# backplane.net
KiCad netlist of a schematic drawn in EAGLE
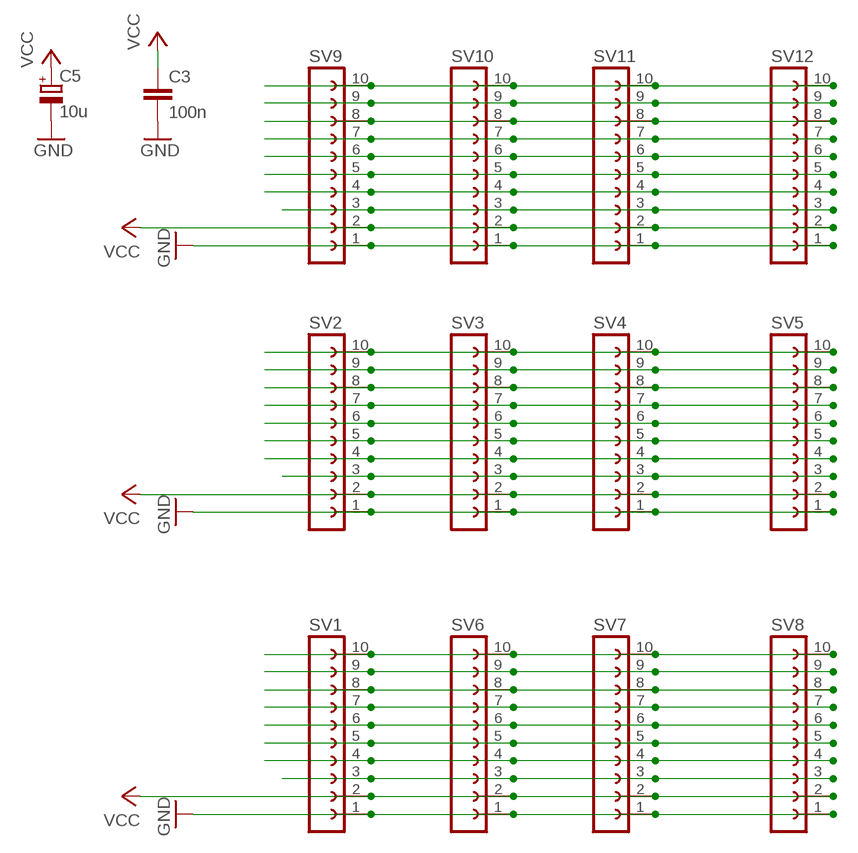
[diagram p0: schematic, sheet 1]

(export (version "E")
  (design (tool "Eeschema 10.0.6"))
  (components
    (comp (ref "C3")
      (value "100n")
      (footprint "eagle-import:C025-024X044")
      (libsource (lib "eagle-import") (part "C-EU025-024X044"))
    )
    (comp (ref "C5")
      (value "10u")
      (footprint "eagle-import:E2,5-6E")
      (libsource (lib "eagle-import") (part "CPOL-EUE2,5-6E"))
    )
    (comp (ref "SV1")
      (value "FE10-1")
      (footprint "eagle-import:FE10")
      (libsource (lib "eagle-import") (part "FE10-1"))
    )
    (comp (ref "SV2")
      (value "FE10-1")
      (footprint "eagle-import:FE10")
      (libsource (lib "eagle-import") (part "FE10-1"))
    )
    (comp (ref "SV3")
      (value "FE10-1")
      (footprint "eagle-import:FE10")
      (libsource (lib "eagle-import") (part "FE10-1"))
    )
    (comp (ref "SV4")
      (value "FE10-1")
      (footprint "eagle-import:FE10")
      (libsource (lib "eagle-import") (part "FE10-1"))
    )
    (comp (ref "SV5")
      (value "FE10-1")
      (footprint "eagle-import:FE10")
      (libsource (lib "eagle-import") (part "FE10-1"))
    )
    (comp (ref "SV6")
      (value "FE10-1")
      (footprint "eagle-import:FE10")
      (libsource (lib "eagle-import") (part "FE10-1"))
    )
    (comp (ref "SV7")
      (value "FE10-1")
      (footprint "eagle-import:FE10")
      (libsource (lib "eagle-import") (part "FE10-1"))
    )
    (comp (ref "SV8")
      (value "FE10-1")
      (footprint "eagle-import:FE10")
      (libsource (lib "eagle-import") (part "FE10-1"))
    )
    (comp (ref "SV9")
      (value "FE10-1")
      (footprint "eagle-import:FE10")
      (libsource (lib "eagle-import") (part "FE10-1"))
    )
    (comp (ref "SV10")
      (value "FE10-1")
      (footprint "eagle-import:FE10")
      (libsource (lib "eagle-import") (part "FE10-1"))
    )
    (comp (ref "SV11")
      (value "FE10-1")
      (footprint "eagle-import:FE10")
      (libsource (lib "eagle-import") (part "FE10-1"))
    )
    (comp (ref "SV12")
      (value "FE10-1")
      (footprint "eagle-import:FE10")
      (libsource (lib "eagle-import") (part "FE10-1"))
    )
  )
  (nets
    (net (code "1") (name "GND") (class "Default")
      (node (ref "C3") (pin "2") (pinfunction "2_2") (pintype "passive"))
      (node (ref "C5") (pin "-") (pinfunction "-_-") (pintype "passive"))
      (node (ref "SV1") (pin "1") (pinfunction "1_1") (pintype "passive"))
      (node (ref "SV10") (pin "1") (pinfunction "1_1") (pintype "passive"))
      (node (ref "SV11") (pin "1") (pinfunction "1_1") (pintype "passive"))
      (node (ref "SV12") (pin "1") (pinfunction "1_1") (pintype "passive"))
      (node (ref "SV2") (pin "1") (pinfunction "1_1") (pintype "passive"))
      (node (ref "SV3") (pin "1") (pinfunction "1_1") (pintype "passive"))
      (node (ref "SV4") (pin "1") (pinfunction "1_1") (pintype "passive"))
      (node (ref "SV5") (pin "1") (pinfunction "1_1") (pintype "passive"))
      (node (ref "SV6") (pin "1") (pinfunction "1_1") (pintype "passive"))
      (node (ref "SV7") (pin "1") (pinfunction "1_1") (pintype "passive"))
      (node (ref "SV8") (pin "1") (pinfunction "1_1") (pintype "passive"))
      (node (ref "SV9") (pin "1") (pinfunction "1_1") (pintype "passive"))
    )
    (net (code "2") (name "Net-(SV1-Pad3)") (class "Default")
      (node (ref "SV1") (pin "3") (pinfunction "3_3") (pintype "passive"))
      (node (ref "SV6") (pin "3") (pinfunction "3_3") (pintype "passive"))
      (node (ref "SV7") (pin "3") (pinfunction "3_3") (pintype "passive"))
      (node (ref "SV8") (pin "3") (pinfunction "3_3") (pintype "passive"))
    )
    (net (code "3") (name "Net-(SV1-Pad4)") (class "Default")
      (node (ref "SV1") (pin "4") (pinfunction "4_4") (pintype "passive"))
      (node (ref "SV6") (pin "4") (pinfunction "4_4") (pintype "passive"))
      (node (ref "SV7") (pin "4") (pinfunction "4_4") (pintype "passive"))
      (node (ref "SV8") (pin "4") (pinfunction "4_4") (pintype "passive"))
    )
    (net (code "4") (name "Net-(SV1-Pad5)") (class "Default")
      (node (ref "SV1") (pin "5") (pinfunction "5_5") (pintype "passive"))
      (node (ref "SV6") (pin "5") (pinfunction "5_5") (pintype "passive"))
      (node (ref "SV7") (pin "5") (pinfunction "5_5") (pintype "passive"))
      (node (ref "SV8") (pin "5") (pinfunction "5_5") (pintype "passive"))
    )
    (net (code "5") (name "Net-(SV1-Pad6)") (class "Default")
      (node (ref "SV1") (pin "6") (pinfunction "6_6") (pintype "passive"))
      (node (ref "SV6") (pin "6") (pinfunction "6_6") (pintype "passive"))
      (node (ref "SV7") (pin "6") (pinfunction "6_6") (pintype "passive"))
      (node (ref "SV8") (pin "6") (pinfunction "6_6") (pintype "passive"))
    )
    (net (code "6") (name "Net-(SV1-Pad7)") (class "Default")
      (node (ref "SV1") (pin "7") (pinfunction "7_7") (pintype "passive"))
      (node (ref "SV6") (pin "7") (pinfunction "7_7") (pintype "passive"))
      (node (ref "SV7") (pin "7") (pinfunction "7_7") (pintype "passive"))
      (node (ref "SV8") (pin "7") (pinfunction "7_7") (pintype "passive"))
    )
    (net (code "7") (name "Net-(SV1-Pad8)") (class "Default")
      (node (ref "SV1") (pin "8") (pinfunction "8_8") (pintype "passive"))
      (node (ref "SV6") (pin "8") (pinfunction "8_8") (pintype "passive"))
      (node (ref "SV7") (pin "8") (pinfunction "8_8") (pintype "passive"))
      (node (ref "SV8") (pin "8") (pinfunction "8_8") (pintype "passive"))
    )
    (net (code "8") (name "Net-(SV1-Pad9)") (class "Default")
      (node (ref "SV1") (pin "9") (pinfunction "9_9") (pintype "passive"))
      (node (ref "SV6") (pin "9") (pinfunction "9_9") (pintype "passive"))
      (node (ref "SV7") (pin "9") (pinfunction "9_9") (pintype "passive"))
      (node (ref "SV8") (pin "9") (pinfunction "9_9") (pintype "passive"))
    )
    (net (code "9") (name "Net-(SV1-Pad10)") (class "Default")
      (node (ref "SV1") (pin "10") (pinfunction "10_10") (pintype "passive"))
      (node (ref "SV6") (pin "10") (pinfunction "10_10") (pintype "passive"))
      (node (ref "SV7") (pin "10") (pinfunction "10_10") (pintype "passive"))
      (node (ref "SV8") (pin "10") (pinfunction "10_10") (pintype "passive"))
    )
    (net (code "10") (name "Net-(SV2-Pad3)") (class "Default")
      (node (ref "SV2") (pin "3") (pinfunction "3_3") (pintype "passive"))
      (node (ref "SV3") (pin "3") (pinfunction "3_3") (pintype "passive"))
      (node (ref "SV4") (pin "3") (pinfunction "3_3") (pintype "passive"))
      (node (ref "SV5") (pin "3") (pinfunction "3_3") (pintype "passive"))
    )
    (net (code "11") (name "Net-(SV2-Pad4)") (class "Default")
      (node (ref "SV2") (pin "4") (pinfunction "4_4") (pintype "passive"))
      (node (ref "SV3") (pin "4") (pinfunction "4_4") (pintype "passive"))
      (node (ref "SV4") (pin "4") (pinfunction "4_4") (pintype "passive"))
      (node (ref "SV5") (pin "4") (pinfunction "4_4") (pintype "passive"))
    )
    (net (code "12") (name "Net-(SV2-Pad5)") (class "Default")
      (node (ref "SV2") (pin "5") (pinfunction "5_5") (pintype "passive"))
      (node (ref "SV3") (pin "5") (pinfunction "5_5") (pintype "passive"))
      (node (ref "SV4") (pin "5") (pinfunction "5_5") (pintype "passive"))
      (node (ref "SV5") (pin "5") (pinfunction "5_5") (pintype "passive"))
    )
    (net (code "13") (name "Net-(SV2-Pad6)") (class "Default")
      (node (ref "SV2") (pin "6") (pinfunction "6_6") (pintype "passive"))
      (node (ref "SV3") (pin "6") (pinfunction "6_6") (pintype "passive"))
      (node (ref "SV4") (pin "6") (pinfunction "6_6") (pintype "passive"))
      (node (ref "SV5") (pin "6") (pinfunction "6_6") (pintype "passive"))
    )
    (net (code "14") (name "Net-(SV2-Pad7)") (class "Default")
      (node (ref "SV2") (pin "7") (pinfunction "7_7") (pintype "passive"))
      (node (ref "SV3") (pin "7") (pinfunction "7_7") (pintype "passive"))
      (node (ref "SV4") (pin "7") (pinfunction "7_7") (pintype "passive"))
      (node (ref "SV5") (pin "7") (pinfunction "7_7") (pintype "passive"))
    )
    (net (code "15") (name "Net-(SV2-Pad8)") (class "Default")
      (node (ref "SV2") (pin "8") (pinfunction "8_8") (pintype "passive"))
      (node (ref "SV3") (pin "8") (pinfunction "8_8") (pintype "passive"))
      (node (ref "SV4") (pin "8") (pinfunction "8_8") (pintype "passive"))
      (node (ref "SV5") (pin "8") (pinfunction "8_8") (pintype "passive"))
    )
    (net (code "16") (name "Net-(SV2-Pad9)") (class "Default")
      (node (ref "SV2") (pin "9") (pinfunction "9_9") (pintype "passive"))
      (node (ref "SV3") (pin "9") (pinfunction "9_9") (pintype "passive"))
      (node (ref "SV4") (pin "9") (pinfunction "9_9") (pintype "passive"))
      (node (ref "SV5") (pin "9") (pinfunction "9_9") (pintype "passive"))
    )
    (net (code "17") (name "Net-(SV2-Pad10)") (class "Default")
      (node (ref "SV2") (pin "10") (pinfunction "10_10") (pintype "passive"))
      (node (ref "SV3") (pin "10") (pinfunction "10_10") (pintype "passive"))
      (node (ref "SV4") (pin "10") (pinfunction "10_10") (pintype "passive"))
      (node (ref "SV5") (pin "10") (pinfunction "10_10") (pintype "passive"))
    )
    (net (code "18") (name "Net-(SV10-Pad3)") (class "Default")
      (node (ref "SV10") (pin "3") (pinfunction "3_3") (pintype "passive"))
      (node (ref "SV11") (pin "3") (pinfunction "3_3") (pintype "passive"))
      (node (ref "SV12") (pin "3") (pinfunction "3_3") (pintype "passive"))
      (node (ref "SV9") (pin "3") (pinfunction "3_3") (pintype "passive"))
    )
    (net (code "19") (name "Net-(SV10-Pad4)") (class "Default")
      (node (ref "SV10") (pin "4") (pinfunction "4_4") (pintype "passive"))
      (node (ref "SV11") (pin "4") (pinfunction "4_4") (pintype "passive"))
      (node (ref "SV12") (pin "4") (pinfunction "4_4") (pintype "passive"))
      (node (ref "SV9") (pin "4") (pinfunction "4_4") (pintype "passive"))
    )
    (net (code "20") (name "Net-(SV10-Pad5)") (class "Default")
      (node (ref "SV10") (pin "5") (pinfunction "5_5") (pintype "passive"))
      (node (ref "SV11") (pin "5") (pinfunction "5_5") (pintype "passive"))
      (node (ref "SV12") (pin "5") (pinfunction "5_5") (pintype "passive"))
      (node (ref "SV9") (pin "5") (pinfunction "5_5") (pintype "passive"))
    )
    (net (code "21") (name "Net-(SV10-Pad6)") (class "Default")
      (node (ref "SV10") (pin "6") (pinfunction "6_6") (pintype "passive"))
      (node (ref "SV11") (pin "6") (pinfunction "6_6") (pintype "passive"))
      (node (ref "SV12") (pin "6") (pinfunction "6_6") (pintype "passive"))
      (node (ref "SV9") (pin "6") (pinfunction "6_6") (pintype "passive"))
    )
    (net (code "22") (name "Net-(SV10-Pad7)") (class "Default")
      (node (ref "SV10") (pin "7") (pinfunction "7_7") (pintype "passive"))
      (node (ref "SV11") (pin "7") (pinfunction "7_7") (pintype "passive"))
      (node (ref "SV12") (pin "7") (pinfunction "7_7") (pintype "passive"))
      (node (ref "SV9") (pin "7") (pinfunction "7_7") (pintype "passive"))
    )
    (net (code "23") (name "Net-(SV10-Pad8)") (class "Default")
      (node (ref "SV10") (pin "8") (pinfunction "8_8") (pintype "passive"))
      (node (ref "SV11") (pin "8") (pinfunction "8_8") (pintype "passive"))
      (node (ref "SV12") (pin "8") (pinfunction "8_8") (pintype "passive"))
      (node (ref "SV9") (pin "8") (pinfunction "8_8") (pintype "passive"))
    )
    (net (code "24") (name "Net-(SV10-Pad9)") (class "Default")
      (node (ref "SV10") (pin "9") (pinfunction "9_9") (pintype "passive"))
      (node (ref "SV11") (pin "9") (pinfunction "9_9") (pintype "passive"))
      (node (ref "SV12") (pin "9") (pinfunction "9_9") (pintype "passive"))
      (node (ref "SV9") (pin "9") (pinfunction "9_9") (pintype "passive"))
    )
    (net (code "25") (name "Net-(SV10-Pad10)") (class "Default")
      (node (ref "SV10") (pin "10") (pinfunction "10_10") (pintype "passive"))
      (node (ref "SV11") (pin "10") (pinfunction "10_10") (pintype "passive"))
      (node (ref "SV12") (pin "10") (pinfunction "10_10") (pintype "passive"))
      (node (ref "SV9") (pin "10") (pinfunction "10_10") (pintype "passive"))
    )
    (net (code "26") (name "VCC") (class "Default")
      (node (ref "C3") (pin "1") (pinfunction "1_1") (pintype "passive"))
      (node (ref "C5") (pin "+") (pinfunction "+_+") (pintype "passive"))
      (node (ref "SV1") (pin "2") (pinfunction "2_2") (pintype "passive"))
      (node (ref "SV10") (pin "2") (pinfunction "2_2") (pintype "passive"))
      (node (ref "SV11") (pin "2") (pinfunction "2_2") (pintype "passive"))
      (node (ref "SV12") (pin "2") (pinfunction "2_2") (pintype "passive"))
      (node (ref "SV2") (pin "2") (pinfunction "2_2") (pintype "passive"))
      (node (ref "SV3") (pin "2") (pinfunction "2_2") (pintype "passive"))
      (node (ref "SV4") (pin "2") (pinfunction "2_2") (pintype "passive"))
      (node (ref "SV5") (pin "2") (pinfunction "2_2") (pintype "passive"))
      (node (ref "SV6") (pin "2") (pinfunction "2_2") (pintype "passive"))
      (node (ref "SV7") (pin "2") (pinfunction "2_2") (pintype "passive"))
      (node (ref "SV8") (pin "2") (pinfunction "2_2") (pintype "passive"))
      (node (ref "SV9") (pin "2") (pinfunction "2_2") (pintype "passive"))
    )
  )
)
